# Main_Board_Teensy.net
KiCad netlist of a schematic drawn in Altium Designer
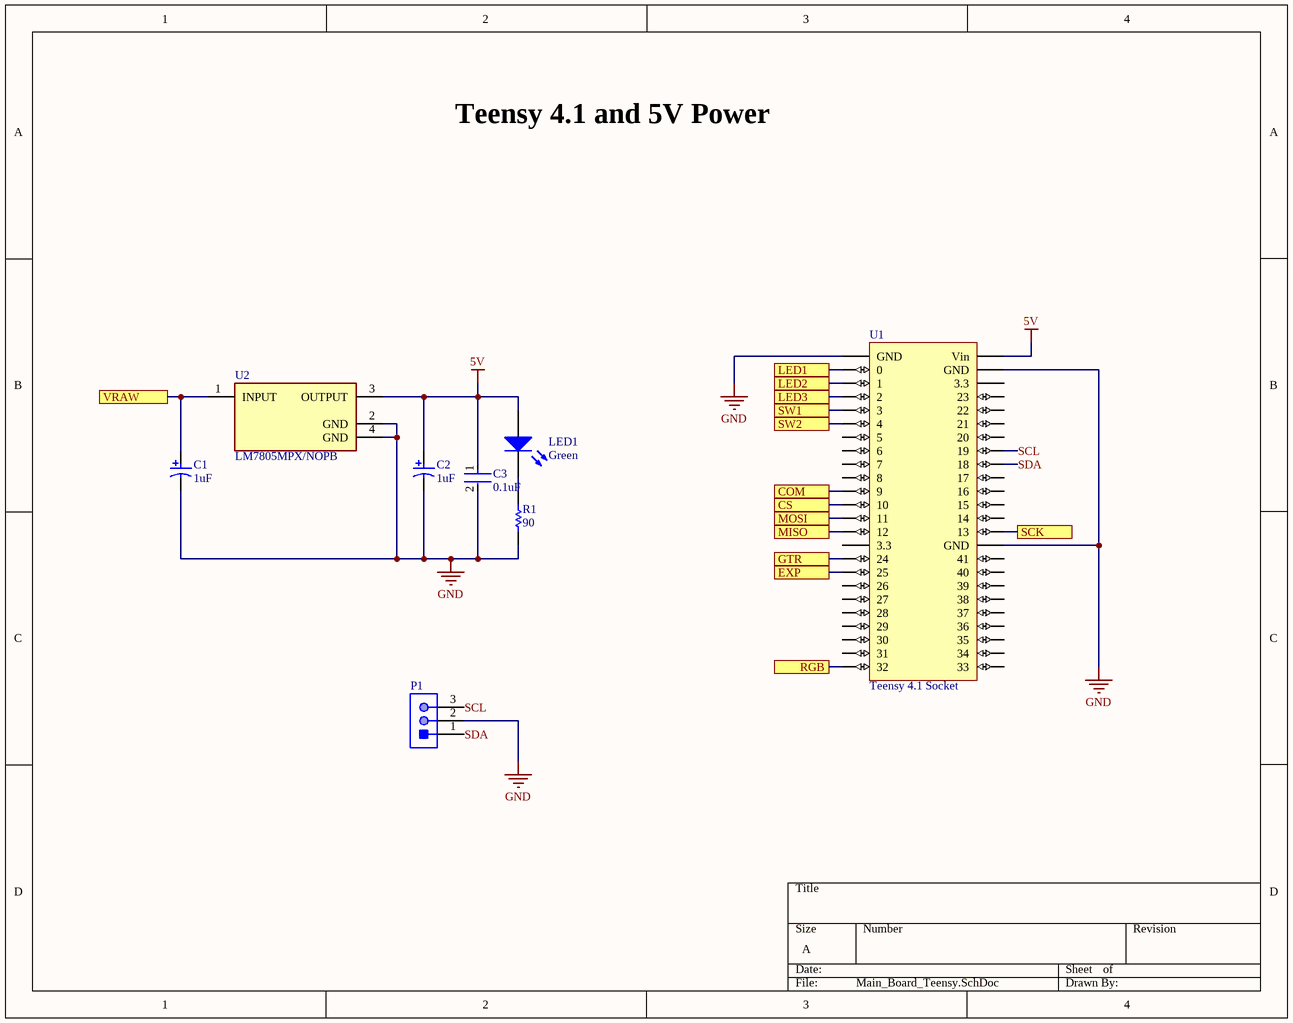
[diagram p0: Main_Board_Teensy.SchDoc]

(export (version "E")
  (design (tool "Eeschema 10.0.6"))
  (components
    (comp (ref "C1")
      (value "1uF")
      (footprint "KEMT-T491-C_L")
      (description "Tantalum Capacitor, 1 uF, +/- 10%, 50 V, -55 to 125 degC, 2-Pin SMD, RoHS, Tape and Reel")
      (fields (field (name "VOLTAGE") "50VDC") (field (name "MANUFACTURER") "Kemet"))
      (libsource (lib "Altium Content Vault") (part "CAP-P-2"))
    )
    (comp (ref "C2")
      (value "1uF")
      (footprint "KEMT-T491-C_L")
      (description "Tantalum Capacitor, 1 uF, +/- 10%, 50 V, -55 to 125 degC, 2-Pin SMD, RoHS, Tape and Reel")
      (fields (field (name "VOLTAGE") "50VDC") (field (name "MANUFACTURER") "Kemet"))
      (libsource (lib "Altium Content Vault") (part "CAP-P-2"))
    )
    (comp (ref "C3")
      (value "0.1uF")
      (footprint "FP-GCM188-0_1-IPC_B")
      (description "Ceramic Capacitor for Automotive 100nF  ±10% 50VDC X8L 0603 Paper T/R")
      (fields (field (name "TOLERANCE") "10%") (field (name "VOLTAGE") "50V"))
      (libsource (lib "Altium Content Vault") (part "02cd4be3c70576c341d710602a673aa"))
    )
    (comp (ref "LED1")
      (value "Green")
      (footprint "0603_A")
      (description "SMD mono-color Chip LED, WL-SMCW, Green")
      (fields (field (name "PARTNUMBER") "150060GS75000") (field (name "MANUFACTURER") "Wuerth Elektronik"))
      (libsource (lib "Altium Content Vault") (part "WE-LED_K1A2-2"))
    )
    (comp (ref "P1")
      (value "B3B-PH-K-S(LF)(SN)")
      (footprint "JST-B3B-PH-K-S-3_V")
      (fields (field (name "MANUFACTURER") "JST"))
      (libsource (lib "Altium Content Vault") (part "CN-1P-M-R3"))
    )
    (comp (ref "R1")
      (value "90")
      (footprint "RESC2013X50X40LL20T20")
      (fields (field (name "MANUFACTURER") "Susumu") (field (name "PART NUMBER") "RR1220P-331-D"))
      (libsource (lib "Altium Content Vault") (part "RES"))
    )
    (comp (ref "U1")
      (value "Teensy 4.1 Socket")
      (footprint "Teensy 4.1 Socket")
      (description "Teensy 4.1")
      (libsource (lib "SDP21_Main_Board_Schematic_Library") (part "Teensy 4.1 Socket"))
    )
    (comp (ref "U2")
      (value "LM7805MPX/NOPB")
      (footprint "FP-LM7805MPX-NOPB-MFG")
      (description "IC REG LINEAR 5V 1.5A SOT223-4")
      (fields
        (field (name "MANUFACTURER") "Texas Instruments")
        (field (name "OCTOPART") "https://octopart.com/lm7805mpx%2Fnopb-texas+instruments-74629992")
      )
      (libsource (lib "Altium Content Vault") (part "b4ee7691a89d8e73302b24c49f391f2"))
    )
  )
  (nets
    (net (code "1") (name "/COM") (class "Default")
      (node (ref "U1") (pin "9") (pinfunction "9_9") (pintype "bidirectional"))
    )
    (net (code "2") (name "/CS") (class "Default")
      (node (ref "U1") (pin "10") (pinfunction "10_10") (pintype "bidirectional"))
    )
    (net (code "3") (name "/EXP") (class "Default")
      (node (ref "U1") (pin "25") (pinfunction "25_25") (pintype "bidirectional"))
    )
    (net (code "4") (name "/GTR") (class "Default")
      (node (ref "U1") (pin "24") (pinfunction "24_24") (pintype "bidirectional"))
    )
    (net (code "5") (name "/LED1") (class "Default")
      (node (ref "U1") (pin "0") (pinfunction "0_0") (pintype "bidirectional"))
    )
    (net (code "6") (name "/LED2") (class "Default")
      (node (ref "U1") (pin "1") (pinfunction "1_1") (pintype "bidirectional"))
    )
    (net (code "7") (name "/LED3") (class "Default")
      (node (ref "U1") (pin "2") (pinfunction "2_2") (pintype "bidirectional"))
    )
    (net (code "8") (name "/MISO") (class "Default")
      (node (ref "U1") (pin "12") (pinfunction "12_12") (pintype "bidirectional"))
    )
    (net (code "9") (name "/MOSI") (class "Default")
      (node (ref "U1") (pin "11") (pinfunction "11_11") (pintype "bidirectional"))
    )
    (net (code "10") (name "/RGB") (class "Default")
      (node (ref "U1") (pin "32") (pinfunction "32_32") (pintype "bidirectional"))
    )
    (net (code "11") (name "/SCK") (class "Default")
      (node (ref "U1") (pin "13") (pinfunction "13_13") (pintype "bidirectional"))
    )
    (net (code "12") (name "/SCL") (class "Default")
      (node (ref "P1") (pin "3") (pinfunction "3_3") (pintype "passive"))
      (node (ref "U1") (pin "19") (pinfunction "19_19") (pintype "bidirectional"))
    )
    (net (code "13") (name "/SDA") (class "Default")
      (node (ref "P1") (pin "1") (pinfunction "1_1") (pintype "passive"))
      (node (ref "U1") (pin "18") (pinfunction "18_18") (pintype "bidirectional"))
    )
    (net (code "14") (name "/SW1") (class "Default")
      (node (ref "U1") (pin "3") (pinfunction "3_3") (pintype "bidirectional"))
    )
    (net (code "15") (name "/SW2") (class "Default")
      (node (ref "U1") (pin "4") (pinfunction "4_4") (pintype "bidirectional"))
    )
    (net (code "16") (name "/VRAW") (class "Default")
      (node (ref "C1") (pin "1") (pinfunction "1_1") (pintype "passive"))
      (node (ref "U2") (pin "1") (pinfunction "INPUT_1") (pintype "power_in"))
    )
    (net (code "17") (name "5V") (class "Default")
      (node (ref "C2") (pin "1") (pinfunction "1_1") (pintype "passive"))
      (node (ref "C3") (pin "1") (pinfunction "1_1") (pintype "passive"))
      (node (ref "LED1") (pin "2") (pinfunction "A_2") (pintype "passive"))
      (node (ref "U1") (pin "Vin") (pinfunction "Vin_Vin") (pintype "power_in"))
      (node (ref "U2") (pin "3") (pinfunction "OUTPUT_3") (pintype "passive"))
    )
    (net (code "18") (name "GND") (class "Default")
      (node (ref "C1") (pin "2") (pinfunction "2_2") (pintype "passive"))
      (node (ref "C2") (pin "2") (pinfunction "2_2") (pintype "passive"))
      (node (ref "C3") (pin "2") (pinfunction "2_2") (pintype "passive"))
      (node (ref "P1") (pin "2") (pinfunction "2_2") (pintype "passive"))
      (node (ref "R1") (pin "1") (pinfunction "1_1") (pintype "passive"))
      (node (ref "U1") (pin "GND1") (pinfunction "GND_GND1") (pintype "power_in"))
      (node (ref "U1") (pin "GND2") (pinfunction "GND_GND2") (pintype "power_in"))
      (node (ref "U1") (pin "GND3") (pinfunction "GND_GND3") (pintype "power_in"))
      (node (ref "U2") (pin "2") (pinfunction "GND_2") (pintype "power_in"))
      (node (ref "U2") (pin "4") (pinfunction "GND_4") (pintype "power_in"))
    )
    (net (code "19") (name "Net-(LED1-K)") (class "Default")
      (node (ref "LED1") (pin "1") (pinfunction "K_1") (pintype "passive"))
      (node (ref "R1") (pin "2") (pinfunction "2_2") (pintype "passive"))
    )
    (net (code "20") (name "unconnected-(U1-3.3-Pad3.3-1)") (class "Default")
      (node (ref "U1") (pin "3.3-1") (pinfunction "3.3_3.3-1") (pintype "power_in"))
    )
    (net (code "21") (name "unconnected-(U1-3.3-Pad3.3-2)") (class "Default")
      (node (ref "U1") (pin "3.3-2") (pinfunction "3.3_3.3-2") (pintype "power_in"))
    )
    (net (code "22") (name "unconnected-(U1-Pad5)") (class "Default")
      (node (ref "U1") (pin "5") (pinfunction "5_5") (pintype "bidirectional"))
    )
    (net (code "23") (name "unconnected-(U1-Pad6)") (class "Default")
      (node (ref "U1") (pin "6") (pinfunction "6_6") (pintype "bidirectional"))
    )
    (net (code "24") (name "unconnected-(U1-Pad7)") (class "Default")
      (node (ref "U1") (pin "7") (pinfunction "7_7") (pintype "bidirectional"))
    )
    (net (code "25") (name "unconnected-(U1-Pad8)") (class "Default")
      (node (ref "U1") (pin "8") (pinfunction "8_8") (pintype "bidirectional"))
    )
    (net (code "26") (name "unconnected-(U1-Pad14)") (class "Default")
      (node (ref "U1") (pin "14") (pinfunction "14_14") (pintype "bidirectional"))
    )
    (net (code "27") (name "unconnected-(U1-Pad15)") (class "Default")
      (node (ref "U1") (pin "15") (pinfunction "15_15") (pintype "bidirectional"))
    )
    (net (code "28") (name "unconnected-(U1-Pad16)") (class "Default")
      (node (ref "U1") (pin "16") (pinfunction "16_16") (pintype "bidirectional"))
    )
    (net (code "29") (name "unconnected-(U1-Pad17)") (class "Default")
      (node (ref "U1") (pin "17") (pinfunction "17_17") (pintype "bidirectional"))
    )
    (net (code "30") (name "unconnected-(U1-Pad20)") (class "Default")
      (node (ref "U1") (pin "20") (pinfunction "20_20") (pintype "bidirectional"))
    )
    (net (code "31") (name "unconnected-(U1-Pad21)") (class "Default")
      (node (ref "U1") (pin "21") (pinfunction "21_21") (pintype "bidirectional"))
    )
    (net (code "32") (name "unconnected-(U1-Pad22)") (class "Default")
      (node (ref "U1") (pin "22") (pinfunction "22_22") (pintype "bidirectional"))
    )
    (net (code "33") (name "unconnected-(U1-Pad23)") (class "Default")
      (node (ref "U1") (pin "23") (pinfunction "23_23") (pintype "bidirectional"))
    )
    (net (code "34") (name "unconnected-(U1-Pad26)") (class "Default")
      (node (ref "U1") (pin "26") (pinfunction "26_26") (pintype "bidirectional"))
    )
    (net (code "35") (name "unconnected-(U1-Pad27)") (class "Default")
      (node (ref "U1") (pin "27") (pinfunction "27_27") (pintype "bidirectional"))
    )
    (net (code "36") (name "unconnected-(U1-Pad28)") (class "Default")
      (node (ref "U1") (pin "28") (pinfunction "28_28") (pintype "bidirectional"))
    )
    (net (code "37") (name "unconnected-(U1-Pad29)") (class "Default")
      (node (ref "U1") (pin "29") (pinfunction "29_29") (pintype "bidirectional"))
    )
    (net (code "38") (name "unconnected-(U1-Pad30)") (class "Default")
      (node (ref "U1") (pin "30") (pinfunction "30_30") (pintype "bidirectional"))
    )
    (net (code "39") (name "unconnected-(U1-Pad31)") (class "Default")
      (node (ref "U1") (pin "31") (pinfunction "31_31") (pintype "bidirectional"))
    )
    (net (code "40") (name "unconnected-(U1-Pad33)") (class "Default")
      (node (ref "U1") (pin "33") (pinfunction "33_33") (pintype "bidirectional"))
    )
    (net (code "41") (name "unconnected-(U1-Pad34)") (class "Default")
      (node (ref "U1") (pin "34") (pinfunction "34_34") (pintype "bidirectional"))
    )
    (net (code "42") (name "unconnected-(U1-Pad35)") (class "Default")
      (node (ref "U1") (pin "35") (pinfunction "35_35") (pintype "bidirectional"))
    )
    (net (code "43") (name "unconnected-(U1-Pad36)") (class "Default")
      (node (ref "U1") (pin "36") (pinfunction "36_36") (pintype "bidirectional"))
    )
    (net (code "44") (name "unconnected-(U1-Pad37)") (class "Default")
      (node (ref "U1") (pin "37") (pinfunction "37_37") (pintype "bidirectional"))
    )
    (net (code "45") (name "unconnected-(U1-Pad38)") (class "Default")
      (node (ref "U1") (pin "38") (pinfunction "38_38") (pintype "bidirectional"))
    )
    (net (code "46") (name "unconnected-(U1-Pad39)") (class "Default")
      (node (ref "U1") (pin "39") (pinfunction "39_39") (pintype "bidirectional"))
    )
    (net (code "47") (name "unconnected-(U1-Pad40)") (class "Default")
      (node (ref "U1") (pin "40") (pinfunction "40_40") (pintype "bidirectional"))
    )
    (net (code "48") (name "unconnected-(U1-Pad41)") (class "Default")
      (node (ref "U1") (pin "41") (pinfunction "41_41") (pintype "bidirectional"))
    )
  )
)
